# STM32L4_LoRa.net
KiCad netlist of a schematic drawn in Altium Designer
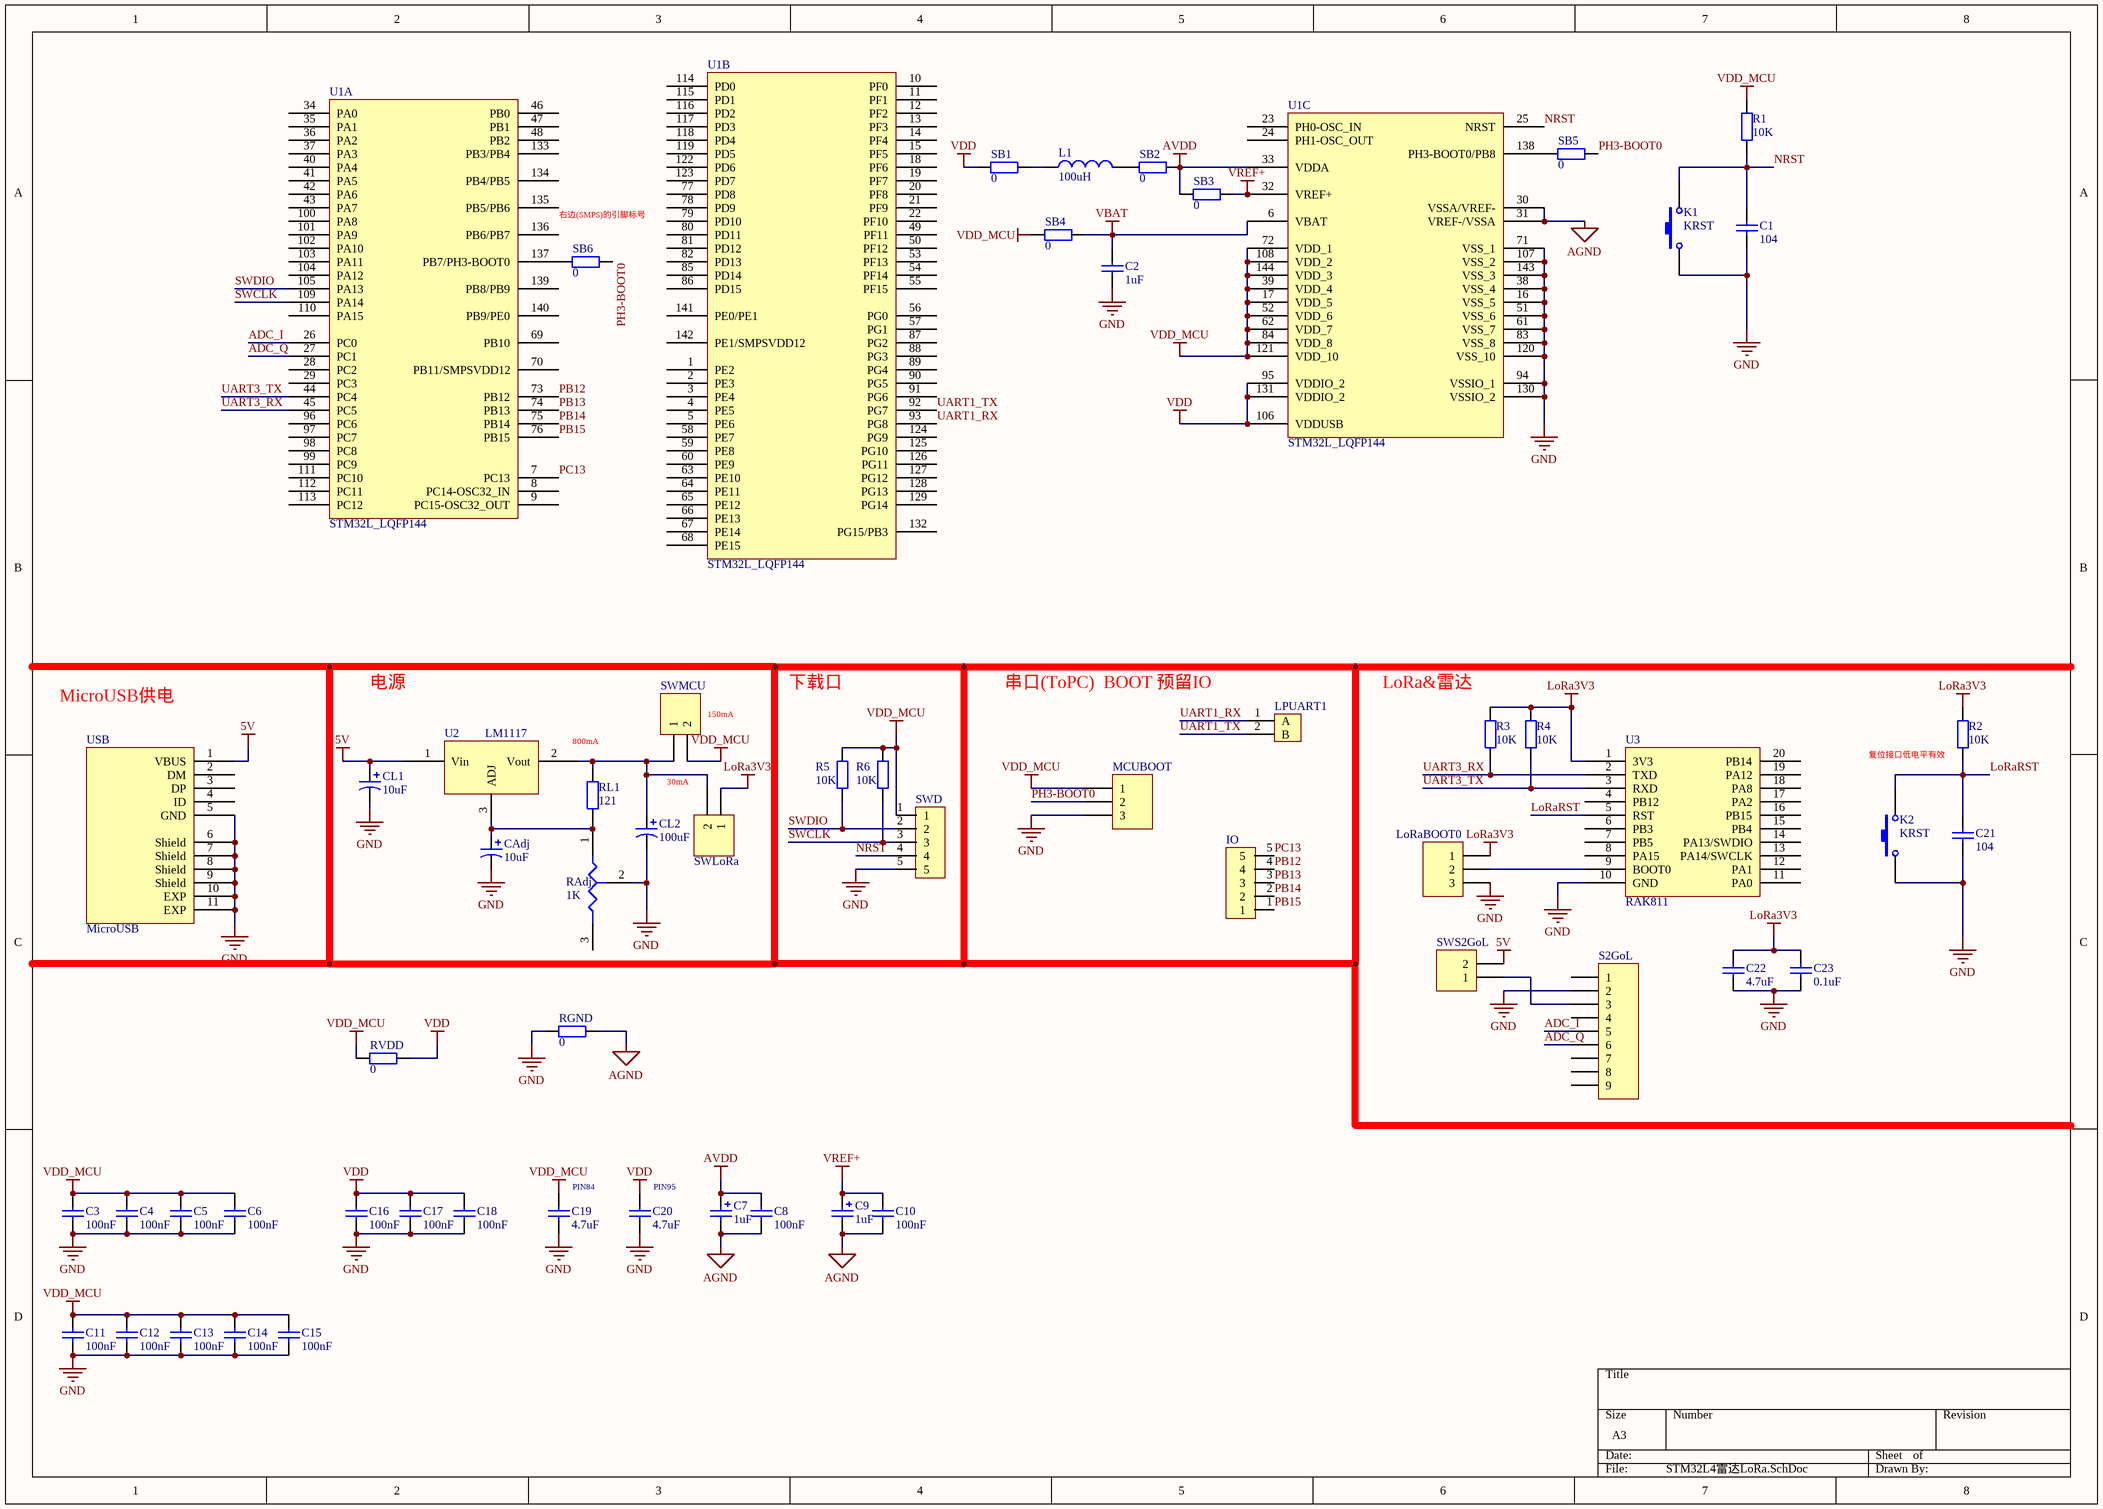
[diagram p0: STM32L4雷达LoRa.SchDoc]

(export (version "E")
  (design (tool "Eeschema 10.0.6"))
  (components
    (comp (ref "C1") (value "104") (footprint "0603C") (libsource (lib "A6-3") (part "贴片电容")))
    (comp (ref "C2") (value "1uF") (footprint "0603C") (libsource (lib "A6-3") (part "贴片电容")))
    (comp (ref "C3") (value "100nF") (footprint "0603C") (libsource (lib "A6-3") (part "贴片电容")))
    (comp (ref "C4") (value "100nF") (footprint "0603C") (libsource (lib "A6-3") (part "贴片电容")))
    (comp (ref "C5") (value "100nF") (footprint "0603C") (libsource (lib "A6-3") (part "贴片电容")))
    (comp (ref "C6") (value "100nF") (footprint "0603C") (libsource (lib "A6-3") (part "贴片电容")))
    (comp (ref "C7") (value "1uF") (footprint "TAN-A") (libsource (lib "A6-3") (part "贴片钽电容")))
    (comp (ref "C8") (value "100nF") (footprint "0603C") (libsource (lib "A6-3") (part "贴片电容")))
    (comp (ref "C9") (value "1uF") (footprint "TAN-A") (libsource (lib "A6-3") (part "贴片钽电容")))
    (comp (ref "C10") (value "100nF") (footprint "0603C") (libsource (lib "A6-3") (part "贴片电容")))
    (comp (ref "C11") (value "100nF") (footprint "0603C") (libsource (lib "A6-3") (part "贴片电容")))
    (comp (ref "C12") (value "100nF") (footprint "0603C") (libsource (lib "A6-3") (part "贴片电容")))
    (comp (ref "C13") (value "100nF") (footprint "0603C") (libsource (lib "A6-3") (part "贴片电容")))
    (comp (ref "C14") (value "100nF") (footprint "0603C") (libsource (lib "A6-3") (part "贴片电容")))
    (comp (ref "C15") (value "100nF") (footprint "0603C") (libsource (lib "A6-3") (part "贴片电容")))
    (comp (ref "C16") (value "100nF") (footprint "0603C") (libsource (lib "A6-3") (part "贴片电容")))
    (comp (ref "C17") (value "100nF") (footprint "0603C") (libsource (lib "A6-3") (part "贴片电容")))
    (comp (ref "C18") (value "100nF") (footprint "0603C") (libsource (lib "A6-3") (part "贴片电容")))
    (comp (ref "C19") (value "4.7uF") (footprint "0603C") (libsource (lib "A6-3") (part "贴片电容")))
    (comp (ref "C20") (value "4.7uF") (footprint "0603C") (libsource (lib "A6-3") (part "贴片电容")))
    (comp (ref "C21") (value "104") (footprint "0603C") (libsource (lib "A6-3") (part "贴片电容")))
    (comp (ref "C22") (value "4.7uF") (footprint "0603C") (libsource (lib "A6-3") (part "贴片电容")))
    (comp (ref "C23") (value "0.1uF") (footprint "0603C") (libsource (lib "A6-3") (part "贴片电容")))
    (comp (ref "CAdj") (value "10uF") (footprint "PCB封装库:极性电容") (libsource (lib "SCH封装库") (part "极性电容")))
    (comp (ref "CL1") (value "10uF") (footprint "PCB封装库:极性电容") (libsource (lib "SCH封装库") (part "极性电容")))
    (comp (ref "CL2") (value "100uF") (footprint "PCB封装库:极性电容") (libsource (lib "SCH封装库") (part "极性电容")))
    (comp (ref "IO") (value "5P") (footprint "5P") (libsource (lib "") (part "5P_1")))
    (comp (ref "K1") (value "KRST") (footprint "四角按键") (libsource (lib "A6-3") (part "四角按键")))
    (comp (ref "K2") (value "KRST") (footprint "四角按键") (libsource (lib "A6-3") (part "四角按键")))
    (comp (ref "L1") (value "100uH") (footprint "Inductor0603L") (libsource (lib "A6-3") (part "Inductor")))
    (comp (ref "LoRaBOOT0")
      (value "Header 3")
      (footprint "HDR1X3")
      (description "Header, 3-Pin")
      (fields (field (name "PUBLISHER") "Altium Limited"))
      (libsource (lib "") (part "Header 3_1"))
    )
    (comp (ref "LPUART1") (value "2P") (footprint "SIP2") (libsource (lib "集成库") (part "2P")))
    (comp (ref "MCUBOOT")
      (value "Header 3")
      (footprint "HDR1X3")
      (description "Header, 3-Pin")
      (fields (field (name "PUBLISHER") "Altium Limited"))
      (libsource (lib "Miscellaneous Connectors") (part "Header 3"))
    )
    (comp (ref "R1") (value "10K") (footprint "0603R") (libsource (lib "A6-3") (part "贴片电阻")))
    (comp (ref "R2") (value "10K") (footprint "0603R") (libsource (lib "A6-3") (part "贴片电阻")))
    (comp (ref "R3") (value "10K") (footprint "0603R") (libsource (lib "A6-3") (part "贴片电阻")))
    (comp (ref "R4") (value "10K") (footprint "0603R") (libsource (lib "A6-3") (part "贴片电阻")))
    (comp (ref "R5") (value "10K") (footprint "0603R") (libsource (lib "A6-3") (part "贴片电阻")))
    (comp (ref "R6") (value "10K") (footprint "0603R") (libsource (lib "A6-3") (part "贴片电阻")))
    (comp (ref "RAdj") (value "1K") (footprint "电位器") (libsource (lib "A6-3") (part "电位器")))
    (comp (ref "RGND") (value "0") (footprint "0603R") (libsource (lib "") (part "贴片电阻_1")))
    (comp (ref "RL1") (value "121") (footprint "0603R") (libsource (lib "A6-3") (part "贴片电阻")))
    (comp (ref "RVDD") (value "0") (footprint "0603R") (libsource (lib "") (part "贴片电阻_1")))
    (comp (ref "S2GoL")
      (value "Header 9")
      (footprint "HDR1X9")
      (description "Header, 9-Pin")
      (fields (field (name "PUBLISHER") "Altium Limited"))
      (libsource (lib "Miscellaneous Connectors") (part "Header 9"))
    )
    (comp (ref "SB1") (value "0") (footprint "0603R") (libsource (lib "") (part "贴片电阻_1")))
    (comp (ref "SB2") (value "0") (footprint "0603R") (libsource (lib "") (part "贴片电阻_1")))
    (comp (ref "SB3") (value "0") (footprint "0603R") (libsource (lib "") (part "贴片电阻_1")))
    (comp (ref "SB4") (value "0") (footprint "0603R") (libsource (lib "") (part "贴片电阻_1")))
    (comp (ref "SB5") (value "0") (footprint "0603R") (libsource (lib "") (part "贴片电阻_1")))
    (comp (ref "SB6") (value "0") (footprint "0603R") (libsource (lib "") (part "贴片电阻_1")))
    (comp (ref "SWD") (value "5P") (footprint "5P") (libsource (lib "集成库") (part "5P")))
    (comp (ref "SWLoRa")
      (value "Header 2")
      (footprint "HDR1X2")
      (description "Header, 2-Pin")
      (fields (field (name "PUBLISHER") "Altium Limited"))
      (libsource (lib "") (part "Header 2_2"))
    )
    (comp (ref "SWMCU")
      (value "Header 2")
      (footprint "HDR1X2")
      (description "Header, 2-Pin")
      (fields (field (name "PUBLISHER") "Altium Limited"))
      (libsource (lib "Miscellaneous Connectors") (part "Header 2"))
    )
    (comp (ref "SWS2GoL")
      (value "Header 2")
      (footprint "HDR1X2")
      (description "Header, 2-Pin")
      (fields (field (name "PUBLISHER") "Altium Limited"))
      (libsource (lib "") (part "Header 2_1"))
    )
    (comp (ref "U1")
      (value "STM32L_LQFP144")
      (footprint "STM32L496LQFP144")
      (libsource (lib "A6-3") (part "STM32L496"))
    )
    (comp (ref "U2") (value "LM1117") (footprint "A6-3:LM1117") (libsource (lib "A6-3") (part "LM1117")))
    (comp (ref "U3")
      (value "RAK811")
      (footprint "RAK811Breakout")
      (libsource (lib "A6-3") (part "RAK811Breakout"))
    )
    (comp (ref "USB") (value "MicroUSB") (footprint "MicroUSB") (libsource (lib "A6-3") (part "MicroUSB")))
  )
  (nets
    (net (code "1") (name "/ADC_I") (class "Default")
      (node (ref "S2GoL") (pin "5") (pinfunction "5_5") (pintype "passive"))
      (node (ref "U1") (pin "26") (pinfunction "PC0_26") (pintype "passive"))
    )
    (net (code "2") (name "/ADC_Q") (class "Default")
      (node (ref "S2GoL") (pin "6") (pinfunction "6_6") (pintype "passive"))
      (node (ref "U1") (pin "27") (pinfunction "PC1_27") (pintype "passive"))
    )
    (net (code "3") (name "/LoRaRST") (class "Default")
      (node (ref "C21") (pin "2") (pinfunction "2_2") (pintype "passive"))
      (node (ref "K2") (pin "2") (pinfunction "2_2") (pintype "passive"))
      (node (ref "R2") (pin "1") (pinfunction "1_1") (pintype "passive"))
      (node (ref "U3") (pin "5") (pinfunction "RST_5") (pintype "passive"))
    )
    (net (code "4") (name "/NRST") (class "Default")
      (node (ref "C1") (pin "2") (pinfunction "2_2") (pintype "passive"))
      (node (ref "K1") (pin "2") (pinfunction "2_2") (pintype "passive"))
      (node (ref "R1") (pin "1") (pinfunction "1_1") (pintype "passive"))
      (node (ref "SWD") (pin "4") (pinfunction "4_4") (pintype "passive"))
      (node (ref "U1") (pin "25") (pinfunction "NRST_25") (pintype "passive"))
    )
    (net (code "5") (name "/PB12") (class "Default")
      (node (ref "IO") (pin "4") (pinfunction "4_4") (pintype "passive"))
      (node (ref "U1") (pin "73") (pinfunction "PB12_73") (pintype "passive"))
    )
    (net (code "6") (name "/PB13") (class "Default")
      (node (ref "IO") (pin "3") (pinfunction "3_3") (pintype "passive"))
      (node (ref "U1") (pin "74") (pinfunction "PB13_74") (pintype "passive"))
    )
    (net (code "7") (name "/PB14") (class "Default")
      (node (ref "IO") (pin "2") (pinfunction "2_2") (pintype "passive"))
      (node (ref "U1") (pin "75") (pinfunction "PB14_75") (pintype "passive"))
    )
    (net (code "8") (name "/PB15") (class "Default")
      (node (ref "IO") (pin "1") (pinfunction "1_1") (pintype "passive"))
      (node (ref "U1") (pin "76") (pinfunction "PB15_76") (pintype "passive"))
    )
    (net (code "9") (name "/PC13") (class "Default")
      (node (ref "IO") (pin "5") (pinfunction "5_5") (pintype "passive"))
      (node (ref "U1") (pin "7") (pinfunction "PC13_7") (pintype "passive"))
    )
    (net (code "10") (name "/PH3-BOOT0") (class "Default")
      (node (ref "MCUBOOT") (pin "2") (pinfunction "2_2") (pintype "passive"))
      (node (ref "SB5") (pin "2") (pinfunction "2_2") (pintype "passive"))
      (node (ref "SB6") (pin "2") (pinfunction "2_2") (pintype "passive"))
    )
    (net (code "11") (name "/SWCLK") (class "Default")
      (node (ref "R6") (pin "1") (pinfunction "1_1") (pintype "passive"))
      (node (ref "SWD") (pin "3") (pinfunction "3_3") (pintype "passive"))
      (node (ref "U1") (pin "109") (pinfunction "PA14_109") (pintype "passive"))
    )
    (net (code "12") (name "/SWDIO") (class "Default")
      (node (ref "R5") (pin "1") (pinfunction "1_1") (pintype "passive"))
      (node (ref "SWD") (pin "2") (pinfunction "2_2") (pintype "passive"))
      (node (ref "U1") (pin "105") (pinfunction "PA13_105") (pintype "passive"))
    )
    (net (code "13") (name "/UART1_RX") (class "Default")
      (node (ref "LPUART1") (pin "1") (pinfunction "A_1") (pintype "passive"))
      (node (ref "U1") (pin "93") (pinfunction "PG8_93") (pintype "passive"))
    )
    (net (code "14") (name "/UART1_TX") (class "Default")
      (node (ref "LPUART1") (pin "2") (pinfunction "B_2") (pintype "passive"))
      (node (ref "U1") (pin "92") (pinfunction "PG7_92") (pintype "passive"))
    )
    (net (code "15") (name "/UART3_RX") (class "Default")
      (node (ref "R3") (pin "1") (pinfunction "1_1") (pintype "passive"))
      (node (ref "U1") (pin "45") (pinfunction "PC5_45") (pintype "passive"))
      (node (ref "U3") (pin "2") (pinfunction "TXD_2") (pintype "passive"))
    )
    (net (code "16") (name "/UART3_TX") (class "Default")
      (node (ref "R4") (pin "1") (pinfunction "1_1") (pintype "passive"))
      (node (ref "U1") (pin "44") (pinfunction "PC4_44") (pintype "passive"))
      (node (ref "U3") (pin "3") (pinfunction "RXD_3") (pintype "passive"))
    )
    (net (code "17") (name "5V") (class "Default")
      (node (ref "CL1") (pin "1") (pinfunction "1_1") (pintype "passive"))
      (node (ref "SWS2GoL") (pin "2") (pinfunction "2_2") (pintype "passive"))
      (node (ref "U2") (pin "1") (pinfunction "Vin_1") (pintype "passive"))
      (node (ref "USB") (pin "1") (pinfunction "VBUS_1") (pintype "passive"))
    )
    (net (code "18") (name "AGND") (class "Default")
      (node (ref "C10") (pin "1") (pinfunction "1_1") (pintype "passive"))
      (node (ref "C7") (pin "2") (pinfunction "2_2") (pintype "passive"))
      (node (ref "C8") (pin "1") (pinfunction "1_1") (pintype "passive"))
      (node (ref "C9") (pin "2") (pinfunction "2_2") (pintype "passive"))
      (node (ref "RGND") (pin "2") (pinfunction "2_2") (pintype "passive"))
      (node (ref "U1") (pin "30") (pinfunction "VSSA/VREF-_30") (pintype "passive"))
      (node (ref "U1") (pin "31") (pinfunction "VREF-/VSSA_31") (pintype "passive"))
    )
    (net (code "19") (name "AVDD") (class "Default")
      (node (ref "C7") (pin "1") (pinfunction "1_1") (pintype "passive"))
      (node (ref "C8") (pin "2") (pinfunction "2_2") (pintype "passive"))
      (node (ref "SB2") (pin "2") (pinfunction "2_2") (pintype "passive"))
      (node (ref "SB3") (pin "1") (pinfunction "1_1") (pintype "passive"))
      (node (ref "U1") (pin "33") (pinfunction "VDDA_33") (pintype "passive"))
    )
    (net (code "20") (name "GND") (class "Default")
      (node (ref "C1") (pin "1") (pinfunction "1_1") (pintype "passive"))
      (node (ref "C11") (pin "1") (pinfunction "1_1") (pintype "passive"))
      (node (ref "C12") (pin "1") (pinfunction "1_1") (pintype "passive"))
      (node (ref "C13") (pin "1") (pinfunction "1_1") (pintype "passive"))
      (node (ref "C14") (pin "1") (pinfunction "1_1") (pintype "passive"))
      (node (ref "C15") (pin "1") (pinfunction "1_1") (pintype "passive"))
      (node (ref "C16") (pin "1") (pinfunction "1_1") (pintype "passive"))
      (node (ref "C17") (pin "1") (pinfunction "1_1") (pintype "passive"))
      (node (ref "C18") (pin "1") (pinfunction "1_1") (pintype "passive"))
      (node (ref "C19") (pin "1") (pinfunction "1_1") (pintype "passive"))
      (node (ref "C2") (pin "1") (pinfunction "1_1") (pintype "passive"))
      (node (ref "C20") (pin "1") (pinfunction "1_1") (pintype "passive"))
      (node (ref "C21") (pin "1") (pinfunction "1_1") (pintype "passive"))
      (node (ref "C22") (pin "1") (pinfunction "1_1") (pintype "passive"))
      (node (ref "C23") (pin "1") (pinfunction "1_1") (pintype "passive"))
      (node (ref "C3") (pin "1") (pinfunction "1_1") (pintype "passive"))
      (node (ref "C4") (pin "1") (pinfunction "1_1") (pintype "passive"))
      (node (ref "C5") (pin "1") (pinfunction "1_1") (pintype "passive"))
      (node (ref "C6") (pin "1") (pinfunction "1_1") (pintype "passive"))
      (node (ref "CAdj") (pin "2") (pinfunction "2_2") (pintype "passive"))
      (node (ref "CL1") (pin "2") (pinfunction "2_2") (pintype "passive"))
      (node (ref "CL2") (pin "2") (pinfunction "2_2") (pintype "passive"))
      (node (ref "K1") (pin "1") (pinfunction "1_1") (pintype "passive"))
      (node (ref "K2") (pin "1") (pinfunction "1_1") (pintype "passive"))
      (node (ref "LoRaBOOT0") (pin "3") (pinfunction "3_3") (pintype "passive"))
      (node (ref "MCUBOOT") (pin "3") (pinfunction "3_3") (pintype "passive"))
      (node (ref "RAdj") (pin "2") (pinfunction "TAP_2") (pintype "passive"))
      (node (ref "RGND") (pin "1") (pinfunction "1_1") (pintype "passive"))
      (node (ref "S2GoL") (pin "2") (pinfunction "2_2") (pintype "passive"))
      (node (ref "SWD") (pin "5") (pinfunction "5_5") (pintype "passive"))
      (node (ref "U1") (pin "107") (pinfunction "VSS_2_107") (pintype "passive"))
      (node (ref "U1") (pin "120") (pinfunction "VSS_10_120") (pintype "passive"))
      (node (ref "U1") (pin "130") (pinfunction "VSSIO_2_130") (pintype "passive"))
      (node (ref "U1") (pin "143") (pinfunction "VSS_3_143") (pintype "passive"))
      (node (ref "U1") (pin "16") (pinfunction "VSS_5_16") (pintype "passive"))
      (node (ref "U1") (pin "38") (pinfunction "VSS_4_38") (pintype "passive"))
      (node (ref "U1") (pin "51") (pinfunction "VSS_6_51") (pintype "passive"))
      (node (ref "U1") (pin "61") (pinfunction "VSS_7_61") (pintype "passive"))
      (node (ref "U1") (pin "71") (pinfunction "VSS_1_71") (pintype "passive"))
      (node (ref "U1") (pin "83") (pinfunction "VSS_8_83") (pintype "passive"))
      (node (ref "U1") (pin "94") (pinfunction "VSSIO_1_94") (pintype "passive"))
      (node (ref "U3") (pin "10") (pinfunction "GND_10") (pintype "passive"))
      (node (ref "USB") (pin "10") (pinfunction "EXP_10") (pintype "passive"))
      (node (ref "USB") (pin "11") (pinfunction "EXP_11") (pintype "passive"))
      (node (ref "USB") (pin "5") (pinfunction "GND_5") (pintype "passive"))
      (node (ref "USB") (pin "6") (pinfunction "Shield_6") (pintype "passive"))
      (node (ref "USB") (pin "7") (pinfunction "Shield_7") (pintype "passive"))
      (node (ref "USB") (pin "8") (pinfunction "Shield_8") (pintype "passive"))
      (node (ref "USB") (pin "9") (pinfunction "Shield_9") (pintype "passive"))
    )
    (net (code "21") (name "LoRa3V3") (class "Default")
      (node (ref "C22") (pin "2") (pinfunction "2_2") (pintype "passive"))
      (node (ref "C23") (pin "2") (pinfunction "2_2") (pintype "passive"))
      (node (ref "LoRaBOOT0") (pin "1") (pinfunction "1_1") (pintype "passive"))
      (node (ref "R2") (pin "2") (pinfunction "2_2") (pintype "passive"))
      (node (ref "R3") (pin "2") (pinfunction "2_2") (pintype "passive"))
      (node (ref "R4") (pin "2") (pinfunction "2_2") (pintype "passive"))
      (node (ref "SWLoRa") (pin "1") (pinfunction "1_1") (pintype "passive"))
      (node (ref "U3") (pin "1") (pinfunction "3V3_1") (pintype "passive"))
    )
    (net (code "22") (name "Net-(L1-Pad1)") (class "Default")
      (node (ref "L1") (pin "1") (pinfunction "1_1") (pintype "passive"))
      (node (ref "SB1") (pin "2") (pinfunction "2_2") (pintype "passive"))
    )
    (net (code "23") (name "Net-(L1-Pad2)") (class "Default")
      (node (ref "L1") (pin "2") (pinfunction "2_2") (pintype "passive"))
      (node (ref "SB2") (pin "1") (pinfunction "1_1") (pintype "passive"))
    )
    (net (code "24") (name "Net-(RAdj-A)") (class "Default")
      (node (ref "CAdj") (pin "1") (pinfunction "1_1") (pintype "passive"))
      (node (ref "RAdj") (pin "1") (pinfunction "A_1") (pintype "passive"))
      (node (ref "RL1") (pin "1") (pinfunction "1_1") (pintype "passive"))
      (node (ref "U2") (pin "3") (pinfunction "ADJ_3") (pintype "passive"))
    )
    (net (code "25") (name "Net-(S2GoL-Pad3)") (class "Default")
      (node (ref "S2GoL") (pin "3") (pinfunction "3_3") (pintype "passive"))
      (node (ref "SWS2GoL") (pin "1") (pinfunction "1_1") (pintype "passive"))
    )
    (net (code "26") (name "Net-(U1A-PB7{slash}PH3-BOOT0)") (class "Default")
      (node (ref "SB6") (pin "1") (pinfunction "1_1") (pintype "passive"))
      (node (ref "U1") (pin "137") (pinfunction "PB7/PH3-BOOT0_137") (pintype "passive"))
    )
    (net (code "27") (name "Net-(U1C-PH3-BOOT0{slash}PB8)") (class "Default")
      (node (ref "SB5") (pin "1") (pinfunction "1_1") (pintype "passive"))
      (node (ref "U1") (pin "138") (pinfunction "PH3-BOOT0/PB8_138") (pintype "passive"))
    )
    (net (code "28") (name "Net-(U2-Vout)") (class "Default")
      (node (ref "CL2") (pin "1") (pinfunction "1_1") (pintype "passive"))
      (node (ref "RL1") (pin "2") (pinfunction "2_2") (pintype "passive"))
      (node (ref "SWLoRa") (pin "2") (pinfunction "2_2") (pintype "passive"))
      (node (ref "SWMCU") (pin "1") (pinfunction "1_1") (pintype "passive"))
      (node (ref "U2") (pin "2") (pinfunction "Vout_2") (pintype "passive"))
    )
    (net (code "29") (name "Net-(U3-BOOT0)") (class "Default")
      (node (ref "LoRaBOOT0") (pin "2") (pinfunction "2_2") (pintype "passive"))
      (node (ref "U3") (pin "9") (pinfunction "BOOT0_9") (pintype "passive"))
    )
    (net (code "30") (name "VBAT") (class "Default")
      (node (ref "C2") (pin "2") (pinfunction "2_2") (pintype "passive"))
      (node (ref "SB4") (pin "2") (pinfunction "2_2") (pintype "passive"))
      (node (ref "U1") (pin "6") (pinfunction "VBAT_6") (pintype "passive"))
    )
    (net (code "31") (name "VDD") (class "Default")
      (node (ref "C16") (pin "2") (pinfunction "2_2") (pintype "passive"))
      (node (ref "C17") (pin "2") (pinfunction "2_2") (pintype "passive"))
      (node (ref "C18") (pin "2") (pinfunction "2_2") (pintype "passive"))
      (node (ref "C20") (pin "2") (pinfunction "2_2") (pintype "passive"))
      (node (ref "RVDD") (pin "2") (pinfunction "2_2") (pintype "passive"))
      (node (ref "SB1") (pin "1") (pinfunction "1_1") (pintype "passive"))
      (node (ref "U1") (pin "106") (pinfunction "VDDUSB_106") (pintype "passive"))
      (node (ref "U1") (pin "131") (pinfunction "VDDIO_2_131") (pintype "passive"))
      (node (ref "U1") (pin "95") (pinfunction "VDDIO_2_95") (pintype "passive"))
    )
    (net (code "32") (name "VDD_MCU") (class "Default")
      (node (ref "C11") (pin "2") (pinfunction "2_2") (pintype "passive"))
      (node (ref "C12") (pin "2") (pinfunction "2_2") (pintype "passive"))
      (node (ref "C13") (pin "2") (pinfunction "2_2") (pintype "passive"))
      (node (ref "C14") (pin "2") (pinfunction "2_2") (pintype "passive"))
      (node (ref "C15") (pin "2") (pinfunction "2_2") (pintype "passive"))
      (node (ref "C19") (pin "2") (pinfunction "2_2") (pintype "passive"))
      (node (ref "C3") (pin "2") (pinfunction "2_2") (pintype "passive"))
      (node (ref "C4") (pin "2") (pinfunction "2_2") (pintype "passive"))
      (node (ref "C5") (pin "2") (pinfunction "2_2") (pintype "passive"))
      (node (ref "C6") (pin "2") (pinfunction "2_2") (pintype "passive"))
      (node (ref "MCUBOOT") (pin "1") (pinfunction "1_1") (pintype "passive"))
      (node (ref "R1") (pin "2") (pinfunction "2_2") (pintype "passive"))
      (node (ref "R5") (pin "2") (pinfunction "2_2") (pintype "passive"))
      (node (ref "R6") (pin "2") (pinfunction "2_2") (pintype "passive"))
      (node (ref "RVDD") (pin "1") (pinfunction "1_1") (pintype "passive"))
      (node (ref "SB4") (pin "1") (pinfunction "1_1") (pintype "passive"))
      (node (ref "SWD") (pin "1") (pinfunction "1_1") (pintype "passive"))
      (node (ref "SWMCU") (pin "2") (pinfunction "2_2") (pintype "passive"))
      (node (ref "U1") (pin "108") (pinfunction "VDD_2_108") (pintype "passive"))
      (node (ref "U1") (pin "121") (pinfunction "VDD_10_121") (pintype "passive"))
      (node (ref "U1") (pin "144") (pinfunction "VDD_3_144") (pintype "passive"))
      (node (ref "U1") (pin "17") (pinfunction "VDD_5_17") (pintype "passive"))
      (node (ref "U1") (pin "39") (pinfunction "VDD_4_39") (pintype "passive"))
      (node (ref "U1") (pin "52") (pinfunction "VDD_6_52") (pintype "passive"))
      (node (ref "U1") (pin "62") (pinfunction "VDD_7_62") (pintype "passive"))
      (node (ref "U1") (pin "72") (pinfunction "VDD_1_72") (pintype "passive"))
      (node (ref "U1") (pin "84") (pinfunction "VDD_8_84") (pintype "passive"))
    )
    (net (code "33") (name "VREF+") (class "Default")
      (node (ref "C10") (pin "2") (pinfunction "2_2") (pintype "passive"))
      (node (ref "C9") (pin "1") (pinfunction "1_1") (pintype "passive"))
      (node (ref "SB3") (pin "2") (pinfunction "2_2") (pintype "passive"))
      (node (ref "U1") (pin "32") (pinfunction "VREF+_32") (pintype "passive"))
    )
    (net (code "34") (name "unconnected-(RAdj-B-Pad3)") (class "Default")
      (node (ref "RAdj") (pin "3") (pinfunction "B_3") (pintype "passive"))
    )
    (net (code "35") (name "unconnected-(S2GoL-Pad1)") (class "Default")
      (node (ref "S2GoL") (pin "1") (pinfunction "1_1") (pintype "passive"))
    )
    (net (code "36") (name "unconnected-(S2GoL-Pad4)") (class "Default")
      (node (ref "S2GoL") (pin "4") (pinfunction "4_4") (pintype "passive"))
    )
    (net (code "37") (name "unconnected-(S2GoL-Pad7)") (class "Default")
      (node (ref "S2GoL") (pin "7") (pinfunction "7_7") (pintype "passive"))
    )
    (net (code "38") (name "unconnected-(S2GoL-Pad8)") (class "Default")
      (node (ref "S2GoL") (pin "8") (pinfunction "8_8") (pintype "passive"))
    )
    (net (code "39") (name "unconnected-(S2GoL-Pad9)") (class "Default")
      (node (ref "S2GoL") (pin "9") (pinfunction "9_9") (pintype "passive"))
    )
    (net (code "40") (name "unconnected-(U1A-PA0-Pad34)") (class "Default")
      (node (ref "U1") (pin "34") (pinfunction "PA0_34") (pintype "passive"))
    )
    (net (code "41") (name "unconnected-(U1A-PA1-Pad35)") (class "Default")
      (node (ref "U1") (pin "35") (pinfunction "PA1_35") (pintype "passive"))
    )
    (net (code "42") (name "unconnected-(U1A-PA2-Pad36)") (class "Default")
      (node (ref "U1") (pin "36") (pinfunction "PA2_36") (pintype "passive"))
    )
    (net (code "43") (name "unconnected-(U1A-PA3-Pad37)") (class "Default")
      (node (ref "U1") (pin "37") (pinfunction "PA3_37") (pintype "passive"))
    )
    (net (code "44") (name "unconnected-(U1A-PA4-Pad40)") (class "Default")
      (node (ref "U1") (pin "40") (pinfunction "PA4_40") (pintype "passive"))
    )
    (net (code "45") (name "unconnected-(U1A-PA5-Pad41)") (class "Default")
      (node (ref "U1") (pin "41") (pinfunction "PA5_41") (pintype "passive"))
    )
    (net (code "46") (name "unconnected-(U1A-PA6-Pad42)") (class "Default")
      (node (ref "U1") (pin "42") (pinfunction "PA6_42") (pintype "passive"))
    )
    (net (code "47") (name "unconnected-(U1A-PA7-Pad43)") (class "Default")
      (node (ref "U1") (pin "43") (pinfunction "PA7_43") (pintype "passive"))
    )
    (net (code "48") (name "unconnected-(U1A-PA8-Pad100)") (class "Default")
      (node (ref "U1") (pin "100") (pinfunction "PA8_100") (pintype "passive"))
    )
    (net (code "49") (name "unconnected-(U1A-PA9-Pad101)") (class "Default")
      (node (ref "U1") (pin "101") (pinfunction "PA9_101") (pintype "passive"))
    )
    (net (code "50") (name "unconnected-(U1A-PA10-Pad102)") (class "Default")
      (node (ref "U1") (pin "102") (pinfunction "PA10_102") (pintype "passive"))
    )
    (net (code "51") (name "unconnected-(U1A-PA11-Pad103)") (class "Default")
      (node (ref "U1") (pin "103") (pinfunction "PA11_103") (pintype "passive"))
    )
    (net (code "52") (name "unconnected-(U1A-PA12-Pad104)") (class "Default")
      (node (ref "U1") (pin "104") (pinfunction "PA12_104") (pintype "passive"))
    )
    (net (code "53") (name "unconnected-(U1A-PA15-Pad110)") (class "Default")
      (node (ref "U1") (pin "110") (pinfunction "PA15_110") (pintype "passive"))
    )
    (net (code "54") (name "unconnected-(U1A-PB0-Pad46)") (class "Default")
      (node (ref "U1") (pin "46") (pinfunction "PB0_46") (pintype "passive"))
    )
    (net (code "55") (name "unconnected-(U1A-PB1-Pad47)") (class "Default")
      (node (ref "U1") (pin "47") (pinfunction "PB1_47") (pintype "passive"))
    )
    (net (code "56") (name "unconnected-(U1A-PB2-Pad48)") (class "Default")
      (node (ref "U1") (pin "48") (pinfunction "PB2_48") (pintype "passive"))
    )
    (net (code "57") (name "unconnected-(U1A-PB3{slash}PB4-Pad133)") (class "Default")
      (node (ref "U1") (pin "133") (pinfunction "PB3/PB4_133") (pintype "passive"))
    )
    (net (code "58") (name "unconnected-(U1A-PB4{slash}PB5-Pad134)") (class "Default")
      (node (ref "U1") (pin "134") (pinfunction "PB4/PB5_134") (pintype "passive"))
    )
    (net (code "59") (name "unconnected-(U1A-PB5{slash}PB6-Pad135)") (class "Default")
      (node (ref "U1") (pin "135") (pinfunction "PB5/PB6_135") (pintype "passive"))
    )
    (net (code "60") (name "unconnected-(U1A-PB6{slash}PB7-Pad136)") (class "Default")
      (node (ref "U1") (pin "136") (pinfunction "PB6/PB7_136") (pintype "passive"))
    )
    (net (code "61") (name "unconnected-(U1A-PB8{slash}PB9-Pad139)") (class "Default")
      (node (ref "U1") (pin "139") (pinfunction "PB8/PB9_139") (pintype "passive"))
    )
    (net (code "62") (name "unconnected-(U1A-PB9{slash}PE0-Pad140)") (class "Default")
      (node (ref "U1") (pin "140") (pinfunction "PB9/PE0_140") (pintype "passive"))
    )
    (net (code "63") (name "unconnected-(U1A-PB10-Pad69)") (class "Default")
      (node (ref "U1") (pin "69") (pinfunction "PB10_69") (pintype "passive"))
    )
    (net (code "64") (name "unconnected-(U1A-PB11{slash}SMPSVDD12-Pad70)") (class "Default")
      (node (ref "U1") (pin "70") (pinfunction "PB11/SMPSVDD12_70") (pintype "passive"))
    )
    (net (code "65") (name "unconnected-(U1A-PC2-Pad28)") (class "Default")
      (node (ref "U1") (pin "28") (pinfunction "PC2_28") (pintype "passive"))
    )
    (net (code "66") (name "unconnected-(U1A-PC3-Pad29)") (class "Default")
      (node (ref "U1") (pin "29") (pinfunction "PC3_29") (pintype "passive"))
    )
    (net (code "67") (name "unconnected-(U1A-PC6-Pad96)") (class "Default")
      (node (ref "U1") (pin "96") (pinfunction "PC6_96") (pintype "passive"))
    )
    (net (code "68") (name "unconnected-(U1A-PC7-Pad97)") (class "Default")
      (node (ref "U1") (pin "97") (pinfunction "PC7_97") (pintype "passive"))
    )
    (net (code "69") (name "unconnected-(U1A-PC8-Pad98)") (class "Default")
      (node (ref "U1") (pin "98") (pinfunction "PC8_98") (pintype "passive"))
    )
    (net (code "70") (name "unconnected-(U1A-PC9-Pad99)") (class "Default")
      (node (ref "U1") (pin "99") (pinfunction "PC9_99") (pintype "passive"))
    )
    (net (code "71") (name "unconnected-(U1A-PC10-Pad111)") (class "Default")
      (node (ref "U1") (pin "111") (pinfunction "PC10_111") (pintype "passive"))
    )
    (net (code "72") (name "unconnected-(U1A-PC11-Pad112)") (class "Default")
      (node (ref "U1") (pin "112") (pinfunction "PC11_112") (pintype "passive"))
    )
    (net (code "73") (name "unconnected-(U1A-PC12-Pad113)") (class "Default")
      (node (ref "U1") (pin "113") (pinfunction "PC12_113") (pintype "passive"))
    )
    (net (code "74") (name "unconnected-(U1A-PC14-OSC32_IN-Pad8)") (class "Default")
      (node (ref "U1") (pin "8") (pinfunction "PC14-OSC32_IN_8") (pintype "passive"))
    )
    (net (code "75") (name "unconnected-(U1A-PC15-OSC32_OUT-Pad9)") (class "Default")
      (node (ref "U1") (pin "9") (pinfunction "PC15-OSC32_OUT_9") (pintype "passive"))
    )
    (net (code "76") (name "unconnected-(U1B-PD0-Pad114)") (class "Default")
      (node (ref "U1") (pin "114") (pinfunction "PD0_114") (pintype "passive"))
    )
    (net (code "77") (name "unconnected-(U1B-PD1-Pad115)") (class "Default")
      (node (ref "U1") (pin "115") (pinfunction "PD1_115") (pintype "passive"))
    )
    (net (code "78") (name "unconnected-(U1B-PD2-Pad116)") (class "Default")
      (node (ref "U1") (pin "116") (pinfunction "PD2_116") (pintype "passive"))
    )
    (net (code "79") (name "unconnected-(U1B-PD3-Pad117)") (class "Default")
      (node (ref "U1") (pin "117") (pinfunction "PD3_117") (pintype "passive"))
    )
    (net (code "80") (name "unconnected-(U1B-PD4-Pad118)") (class "Default")
      (node (ref "U1") (pin "118") (pinfunction "PD4_118") (pintype "passive"))
    )
    (net (code "81") (name "unconnected-(U1B-PD5-Pad119)") (class "Default")
      (node (ref "U1") (pin "119") (pinfunction "PD5_119") (pintype "passive"))
    )
    (net (code "82") (name "unconnected-(U1B-PD6-Pad122)") (class "Default")
      (node (ref "U1") (pin "122") (pinfunction "PD6_122") (pintype "passive"))
    )
    (net (code "83") (name "unconnected-(U1B-PD7-Pad123)") (class "Default")
      (node (ref "U1") (pin "123") (pinfunction "PD7_123") (pintype "passive"))
    )
    (net (code "84") (name "unconnected-(U1B-PD8-Pad77)") (class "Default")
      (node (ref "U1") (pin "77") (pinfunction "PD8_77") (pintype "passive"))
    )
    (net (code "85") (name "unconnected-(U1B-PD9-Pad78)") (class "Default")
      (node (ref "U1") (pin "78") (pinfunction "PD9_78") (pintype "passive"))
    )
    (net (code "86") (name "unconnected-(U1B-PD10-Pad79)") (class "Default")
      (node (ref "U1") (pin "79") (pinfunction "PD10_79") (pintype "passive"))
    )
    (net (code "87") (name "unconnected-(U1B-PD11-Pad80)") (class "Default")
      (node (ref "U1") (pin "80") (pinfunction "PD11_80") (pintype "passive"))
    )
    (net (code "88") (name "unconnected-(U1B-PD12-Pad81)") (class "Default")
      (node (ref "U1") (pin "81") (pinfunction "PD12_81") (pintype "passive"))
    )
    (net (code "89") (name "unconnected-(U1B-PD13-Pad82)") (class "Default")
      (node (ref "U1") (pin "82") (pinfunction "PD13_82") (pintype "passive"))
    )
    (net (code "90") (name "unconnected-(U1B-PD14-Pad85)") (class "Default")
      (node (ref "U1") (pin "85") (pinfunction "PD14_85") (pintype "passive"))
    )
    (net (code "91") (name "unconnected-(U1B-PD15-Pad86)") (class "Default")
      (node (ref "U1") (pin "86") (pinfunction "PD15_86") (pintype "passive"))
    )
    (net (code "92") (name "unconnected-(U1B-PE0{slash}PE1-Pad141)") (class "Default")
      (node (ref "U1") (pin "141") (pinfunction "PE0/PE1_141") (pintype "passive"))
    )
    (net (code "93") (name "unconnected-(U1B-PE1{slash}SMPSVDD12-Pad142)") (class "Default")
      (node (ref "U1") (pin "142") (pinfunction "PE1/SMPSVDD12_142") (pintype "passive"))
    )
    (net (code "94") (name "unconnected-(U1B-PE2-Pad1)") (class "Default")
      (node (ref "U1") (pin "1") (pinfunction "PE2_1") (pintype "passive"))
    )
    (net (code "95") (name "unconnected-(U1B-PE3-Pad2)") (class "Default")
      (node (ref "U1") (pin "2") (pinfunction "PE3_2") (pintype "passive"))
    )
    (net (code "96") (name "unconnected-(U1B-PE4-Pad3)") (class "Default")
      (node (ref "U1") (pin "3") (pinfunction "PE4_3") (pintype "passive"))
    )
    (net (code "97") (name "unconnected-(U1B-PE5-Pad4)") (class "Default")
      (node (ref "U1") (pin "4") (pinfunction "PE5_4") (pintype "passive"))
    )
    (net (code "98") (name "unconnected-(U1B-PE6-Pad5)") (class "Default")
      (node (ref "U1") (pin "5") (pinfunction "PE6_5") (pintype "passive"))
    )
    (net (code "99") (name "unconnected-(U1B-PE7-Pad58)") (class "Default")
      (node (ref "U1") (pin "58") (pinfunction "PE7_58") (pintype "passive"))
    )
    (net (code "100") (name "unconnected-(U1B-PE8-Pad59)") (class "Default")
      (node (ref "U1") (pin "59") (pinfunction "PE8_59") (pintype "passive"))
    )
    (net (code "101") (name "unconnected-(U1B-PE9-Pad60)") (class "Default")
      (node (ref "U1") (pin "60") (pinfunction "PE9_60") (pintype "passive"))
    )
    (net (code "102") (name "unconnected-(U1B-PE10-Pad63)") (class "Default")
      (node (ref "U1") (pin "63") (pinfunction "PE10_63") (pintype "passive"))
    )
    (net (code "103") (name "unconnected-(U1B-PE11-Pad64)") (class "Default")
      (node (ref "U1") (pin "64") (pinfunction "PE11_64") (pintype "passive"))
    )
    (net (code "104") (name "unconnected-(U1B-PE12-Pad65)") (class "Default")
      (node (ref "U1") (pin "65") (pinfunction "PE12_65") (pintype "passive"))
    )
    (net (code "105") (name "unconnected-(U1B-PE13-Pad66)") (class "Default")
      (node (ref "U1") (pin "66") (pinfunction "PE13_66") (pintype "passive"))
    )
    (net (code "106") (name "unconnected-(U1B-PE14-Pad67)") (class "Default")
      (node (ref "U1") (pin "67") (pinfunction "PE14_67") (pintype "passive"))
    )
    (net (code "107") (name "unconnected-(U1B-PE15-Pad68)") (class "Default")
      (node (ref "U1") (pin "68") (pinfunction "PE15_68") (pintype "passive"))
    )
    (net (code "108") (name "unconnected-(U1B-PF0-Pad10)") (class "Default")
      (node (ref "U1") (pin "10") (pinfunction "PF0_10") (pintype "passive"))
    )
    (net (code "109") (name "unconnected-(U1B-PF1-Pad11)") (class "Default")
      (node (ref "U1") (pin "11") (pinfunction "PF1_11") (pintype "passive"))
    )
    (net (code "110") (name "unconnected-(U1B-PF2-Pad12)") (class "Default")
      (node (ref "U1") (pin "12") (pinfunction "PF2_12") (pintype "passive"))
    )
    (net (code "111") (name "unconnected-(U1B-PF3-Pad13)") (class "Default")
      (node (ref "U1") (pin "13") (pinfunction "PF3_13") (pintype "passive"))
    )
    (net (code "112") (name "unconnected-(U1B-PF4-Pad14)") (class "Default")
      (node (ref "U1") (pin "14") (pinfunction "PF4_14") (pintype "passive"))
    )
    (net (code "113") (name "unconnected-(U1B-PF5-Pad15)") (class "Default")
      (node (ref "U1") (pin "15") (pinfunction "PF5_15") (pintype "passive"))
    )
    (net (code "114") (name "unconnected-(U1B-PF6-Pad18)") (class "Default")
      (node (ref "U1") (pin "18") (pinfunction "PF6_18") (pintype "passive"))
    )
    (net (code "115") (name "unconnected-(U1B-PF7-Pad19)") (class "Default")
      (node (ref "U1") (pin "19") (pinfunction "PF7_19") (pintype "passive"))
    )
    (net (code "116") (name "unconnected-(U1B-PF8-Pad20)") (class "Default")
      (node (ref "U1") (pin "20") (pinfunction "PF8_20") (pintype "passive"))
    )
    (net (code "117") (name "unconnected-(U1B-PF9-Pad21)") (class "Default")
      (node (ref "U1") (pin "21") (pinfunction "PF9_21") (pintype "passive"))
    )
    (net (code "118") (name "unconnected-(U1B-PF10-Pad22)") (class "Default")
      (node (ref "U1") (pin "22") (pinfunction "PF10_22") (pintype "passive"))
    )
    (net (code "119") (name "unconnected-(U1B-PF11-Pad49)") (class "Default")
      (node (ref "U1") (pin "49") (pinfunction "PF11_49") (pintype "passive"))
    )
    (net (code "120") (name "unconnected-(U1B-PF12-Pad50)") (class "Default")
      (node (ref "U1") (pin "50") (pinfunction "PF12_50") (pintype "passive"))
    )
    (net (code "121") (name "unconnected-(U1B-PF13-Pad53)") (class "Default")
      (node (ref "U1") (pin "53") (pinfunction "PF13_53") (pintype "passive"))
    )
    (net (code "122") (name "unconnected-(U1B-PF14-Pad54)") (class "Default")
      (node (ref "U1") (pin "54") (pinfunction "PF14_54") (pintype "passive"))
    )
    (net (code "123") (name "unconnected-(U1B-PF15-Pad55)") (class "Default")
      (node (ref "U1") (pin "55") (pinfunction "PF15_55") (pintype "passive"))
    )
    (net (code "124") (name "unconnected-(U1B-PG0-Pad56)") (class "Default")
      (node (ref "U1") (pin "56") (pinfunction "PG0_56") (pintype "passive"))
    )
    (net (code "125") (name "unconnected-(U1B-PG1-Pad57)") (class "Default")
      (node (ref "U1") (pin "57") (pinfunction "PG1_57") (pintype "passive"))
    )
    (net (code "126") (name "unconnected-(U1B-PG2-Pad87)") (class "Default")
      (node (ref "U1") (pin "87") (pinfunction "PG2_87") (pintype "passive"))
    )
    (net (code "127") (name "unconnected-(U1B-PG3-Pad88)") (class "Default")
      (node (ref "U1") (pin "88") (pinfunction "PG3_88") (pintype "passive"))
    )
    (net (code "128") (name "unconnected-(U1B-PG4-Pad89)") (class "Default")
      (node (ref "U1") (pin "89") (pinfunction "PG4_89") (pintype "passive"))
    )
    (net (code "129") (name "unconnected-(U1B-PG5-Pad90)") (class "Default")
      (node (ref "U1") (pin "90") (pinfunction "PG5_90") (pintype "passive"))
    )
    (net (code "130") (name "unconnected-(U1B-PG6-Pad91)") (class "Default")
      (node (ref "U1") (pin "91") (pinfunction "PG6_91") (pintype "passive"))
    )
    (net (code "131") (name "unconnected-(U1B-PG9-Pad124)") (class "Default")
      (node (ref "U1") (pin "124") (pinfunction "PG9_124") (pintype "passive"))
    )
    (net (code "132") (name "unconnected-(U1B-PG10-Pad125)") (class "Default")
      (node (ref "U1") (pin "125") (pinfunction "PG10_125") (pintype "passive"))
    )
    (net (code "133") (name "unconnected-(U1B-PG11-Pad126)") (class "Default")
      (node (ref "U1") (pin "126") (pinfunction "PG11_126") (pintype "passive"))
    )
    (net (code "134") (name "unconnected-(U1B-PG12-Pad127)") (class "Default")
      (node (ref "U1") (pin "127") (pinfunction "PG12_127") (pintype "passive"))
    )
    (net (code "135") (name "unconnected-(U1B-PG13-Pad128)") (class "Default")
      (node (ref "U1") (pin "128") (pinfunction "PG13_128") (pintype "passive"))
    )
    (net (code "136") (name "unconnected-(U1B-PG14-Pad129)") (class "Default")
      (node (ref "U1") (pin "129") (pinfunction "PG14_129") (pintype "passive"))
    )
    (net (code "137") (name "unconnected-(U1B-PG15{slash}PB3-Pad132)") (class "Default")
      (node (ref "U1") (pin "132") (pinfunction "PG15/PB3_132") (pintype "passive"))
    )
    (net (code "138") (name "unconnected-(U1C-PH0-OSC_IN-Pad23)") (class "Default")
      (node (ref "U1") (pin "23") (pinfunction "PH0-OSC_IN_23") (pintype "passive"))
    )
    (net (code "139") (name "unconnected-(U1C-PH1-OSC_OUT-Pad24)") (class "Default")
      (node (ref "U1") (pin "24") (pinfunction "PH1-OSC_OUT_24") (pintype "passive"))
    )
    (net (code "140") (name "unconnected-(U3-PA0-Pad11)") (class "Default")
      (node (ref "U3") (pin "11") (pinfunction "PA0_11") (pintype "passive"))
    )
    (net (code "141") (name "unconnected-(U3-PA1-Pad12)") (class "Default")
      (node (ref "U3") (pin "12") (pinfunction "PA1_12") (pintype "passive"))
    )
    (net (code "142") (name "unconnected-(U3-PA2-Pad17)") (class "Default")
      (node (ref "U3") (pin "17") (pinfunction "PA2_17") (pintype "passive"))
    )
    (net (code "143") (name "unconnected-(U3-PA8-Pad18)") (class "Default")
      (node (ref "U3") (pin "18") (pinfunction "PA8_18") (pintype "passive"))
    )
    (net (code "144") (name "unconnected-(U3-PA12-Pad19)") (class "Default")
      (node (ref "U3") (pin "19") (pinfunction "PA12_19") (pintype "passive"))
    )
    (net (code "145") (name "unconnected-(U3-PA13{slash}SWDIO-Pad14)") (class "Default")
      (node (ref "U3") (pin "14") (pinfunction "PA13/SWDIO_14") (pintype "passive"))
    )
    (net (code "146") (name "unconnected-(U3-PA14{slash}SWCLK-Pad13)") (class "Default")
      (node (ref "U3") (pin "13") (pinfunction "PA14/SWCLK_13") (pintype "passive"))
    )
    (net (code "147") (name "unconnected-(U3-PA15-Pad8)") (class "Default")
      (node (ref "U3") (pin "8") (pinfunction "PA15_8") (pintype "passive"))
    )
    (net (code "148") (name "unconnected-(U3-PB3-Pad6)") (class "Default")
      (node (ref "U3") (pin "6") (pinfunction "PB3_6") (pintype "passive"))
    )
    (net (code "149") (name "unconnected-(U3-PB4-Pad15)") (class "Default")
      (node (ref "U3") (pin "15") (pinfunction "PB4_15") (pintype "passive"))
    )
    (net (code "150") (name "unconnected-(U3-PB5-Pad7)") (class "Default")
      (node (ref "U3") (pin "7") (pinfunction "PB5_7") (pintype "passive"))
    )
    (net (code "151") (name "unconnected-(U3-PB12-Pad4)") (class "Default")
      (node (ref "U3") (pin "4") (pinfunction "PB12_4") (pintype "passive"))
    )
    (net (code "152") (name "unconnected-(U3-PB14-Pad20)") (class "Default")
      (node (ref "U3") (pin "20") (pinfunction "PB14_20") (pintype "passive"))
    )
    (net (code "153") (name "unconnected-(U3-PB15-Pad16)") (class "Default")
      (node (ref "U3") (pin "16") (pinfunction "PB15_16") (pintype "passive"))
    )
    (net (code "154") (name "unconnected-(USB-DM-Pad2)") (class "Default")
      (node (ref "USB") (pin "2") (pinfunction "DM_2") (pintype "passive"))
    )
    (net (code "155") (name "unconnected-(USB-DP-Pad3)") (class "Default")
      (node (ref "USB") (pin "3") (pinfunction "DP_3") (pintype "passive"))
    )
    (net (code "156") (name "unconnected-(USB-ID-Pad4)") (class "Default")
      (node (ref "USB") (pin "4") (pinfunction "ID_4") (pintype "passive"))
    )
  )
)
